# 7_SENSORS.net
KiCad netlist of a schematic drawn in Altium Designer
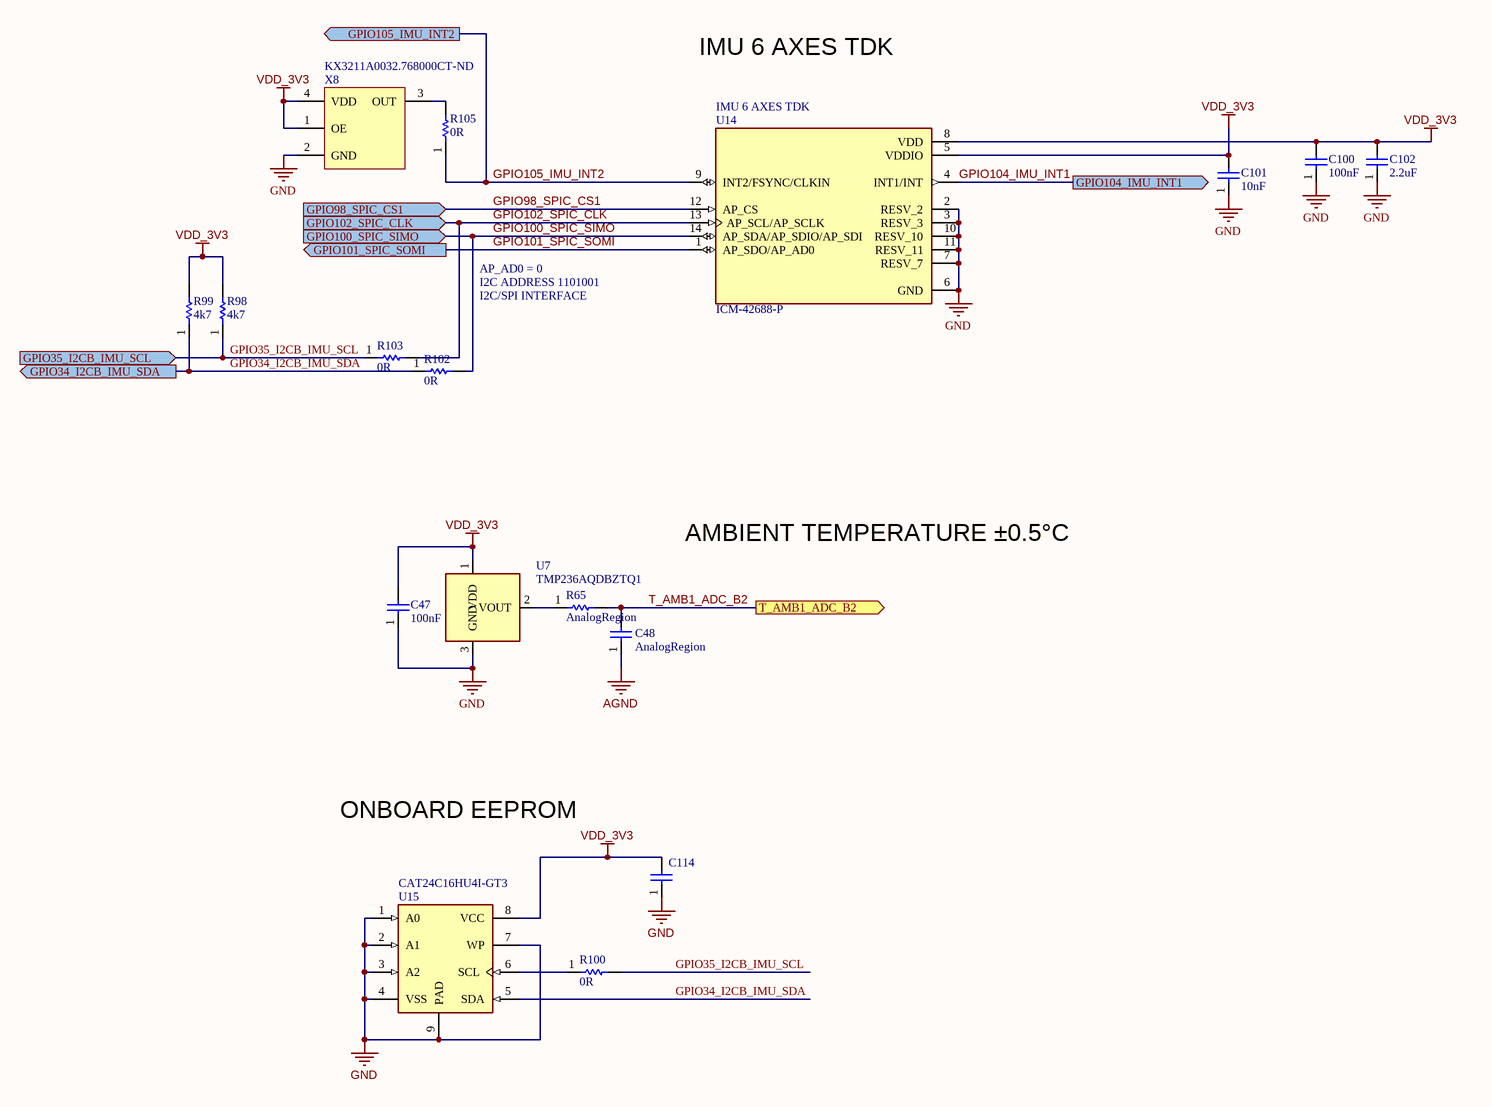
[diagram p0: [7] SENSORS.SchDoc]

(export (version "E")
  (design (tool "Eeschema 10.0.6"))
  (components
    (comp (ref "C47")
      (value "100nF")
      (footprint "CAPC1005X03N(0402)")
      (description "CAP CER 0.1UF 16V X7R 0402")
      (fields (field (name "MPN") "GRM155R71C104JA88D") (field (name "TOLERANCE") "5%"))
      (libsource (lib "IHMC_Altium_Lib") (part "100nF_16V_0402_CAP"))
    )
    (comp (ref "C48")
      (value "GCM1555C1H471JA16D")
      (footprint "CAPC1005X03N(0402)")
      (description "CAP CER 470PF 50V C0G/NP0 0402")
      (fields
        (field (name "TOLERANCE") "5%")
        (field (name "VOLTAGE") "50V")
        (field (name "CLASSNAME") "AnalogRegion")
      )
      (libsource (lib "IHMC_Altium_Lib") (part "470pF_50V_0402_CAP"))
    )
    (comp (ref "C100")
      (value "100nF")
      (footprint "CAPC1005X03N(0402)")
      (description "CAP CER 0.1UF 16V X7R 0402")
      (fields (field (name "MPN") "GRM155R71C104JA88D") (field (name "TOLERANCE") "5%"))
      (libsource (lib "IHMC_Altium_Lib") (part "100nF_16V_0402_CAP"))
    )
    (comp (ref "C101")
      (value "10nF")
      (footprint "CAPC1005X03N(0402)")
      (description "CAP CER 10000PF 50V X7R 0402")
      (fields (field (name "MPN") "CC0402KRX7R9BB103") (field (name "VOLTAGE") "50V"))
      (libsource (lib "IHMC_Altium_Lib") (part "10nF_50V_0402_CAP"))
    )
    (comp (ref "C102")
      (value "2.2uF")
      (footprint "CAPC1608X09N(0603)")
      (description "CAP CER 2.2UF 10V X5R 0603")
      (fields (field (name "MPN") "GRM188R61A225KE34D") (field (name "TOLERANCE") "10%"))
      (libsource (lib "IHMC_Altium_Lib") (part "2.2uF_10V_0603_CAP"))
    )
    (comp (ref "C114")
      (value "GRM155R71C104JA88D")
      (footprint "CAPC1005X03N(0402)")
      (description "CAP CER 0.1UF 16V X7R 0402")
      (fields (field (name "TOLERANCE") "5%"))
      (libsource (lib "IHMC_Altium_Lib") (part "100nF_16V_0402_CAP"))
    )
    (comp (ref "R65")
      (value "CRCW0402220RFKED")
      (footprint "RESC1005X06N(0402)")
      (description "RES SMD 220 OHM 1% 1/16W 0402")
      (fields (field (name "TOLERANCE") "1%.") (field (name "CLASSNAME") "AnalogRegion"))
      (libsource (lib "IHMC_Altium_Lib") (part "220_1/16W_0402_RES"))
    )
    (comp (ref "R98")
      (value "4k7")
      (footprint "RESC1608X09N(0603)")
      (description "RES SMD 4.7K OHM 1% 1/10W 0603")
      (fields (field (name "MPN") "CRCW06034K70FKEA") (field (name "DRAWN BY") "TC"))
      (libsource (lib "IHMC_Altium_Lib") (part "4k7_1/10W_0603_RES"))
    )
    (comp (ref "R99")
      (value "4k7")
      (footprint "RESC1608X09N(0603)")
      (description "RES SMD 4.7K OHM 1% 1/10W 0603")
      (fields (field (name "MPN") "CRCW06034K70FKEA") (field (name "DRAWN BY") "TC"))
      (libsource (lib "IHMC_Altium_Lib") (part "4k7_1/10W_0603_RES"))
    )
    (comp (ref "R100")
      (value "0R")
      (footprint "RESC1608X09N(0603)")
      (description "RES SMD 0 OHM JUMPER 1/10W 0603")
      (fields (field (name "MPN") "RC0603JR-070RL") (field (name "TOLERANCE") "Jumper"))
      (libsource (lib "IHMC_Altium_Lib") (part "0R_1/10W_0603_RES"))
    )
    (comp (ref "R102")
      (value "0R")
      (footprint "0402")
      (fields
        (field (name "MANUFACTURER") "Vishay Dale")
        (field (name "MANUFACTURER PART NUMBER") "RCS04020000Z0ED")
      )
      (libsource (lib "IHMC_Altium_Lib") (part "0R_1/5W_0402_RCS04020000Z0ED_RES"))
    )
    (comp (ref "R103")
      (value "0R")
      (footprint "0402")
      (fields
        (field (name "MANUFACTURER") "Vishay Dale")
        (field (name "MANUFACTURER PART NUMBER") "RCS04020000Z0ED")
      )
      (libsource (lib "IHMC_Altium_Lib") (part "0R_1/5W_0402_RCS04020000Z0ED_RES"))
    )
    (comp (ref "R105")
      (value "0R")
      (footprint "0402")
      (fields
        (field (name "MANUFACTURER") "Vishay Dale")
        (field (name "MANUFACTURER PART NUMBER") "RCS04020000Z0ED")
      )
      (libsource (lib "IHMC_Altium_Lib") (part "0R_1/5W_0402_RCS04020000Z0ED_RES"))
    )
    (comp (ref "U7")
      (value "TMP236AQDBZTQ1")
      (footprint "SOT23")
      (description "TMP23x-Q1 Automotive Grade, High-Accuracy Analog Output Temperature Sensors")
      (fields (field (name "MANUFACTURER") "Texas Instruments"))
      (libsource (lib "IHMC_Altium_Lib") (part "TMP236AQDBZTQ1_TEMP_SENSOR"))
    )
    (comp (ref "U14")
      (value "ICM-42688-P")
      (footprint "PQFN50P300X250X97-14N")
      (description "Accelerometer and Gyroscope 6-Axis MEMS Motion Tracking Device Digital-OUT 14-Pin LGA T/R")
      (fields (field (name "MANUFACTURER") "TDK InvenSense"))
      (libsource (lib "IHMC_Altium_Lib") (part "ICM-42688-P_IMU_6-axes"))
    )
    (comp (ref "U15")
      (value "CAT24C16HU4I-GT3")
      (footprint "UDFN8-EP")
      (description "EEPROM Serial-2Wire 16K-bit 2K x 8 1.8V/2.5V/3.3V/5V Automotive 8-Pin UDFN EP T/R")
      (fields (field (name "MANUFACTURER") "ON Semiconductor"))
      (libsource (lib "IHMC_Altium_Lib") (part "CAT24C16HU4I-GT3_EEPROM_16Kb"))
    )
    (comp (ref "X8")
      (value "32.768Khz_OSC_KX3211A0032.768000")
      (footprint "KX3211A0032.768000")
      (description "SMD Crystal Oscillator 0.032768MHz 3.3V 15pF 4-Pin CSMD")
      (fields
        (field (name "MANUFACTURER") "Diodes")
        (field (name "MANUFACTURER PART NUMBER") "KX3211A0032.768000")
        (field (name "SUPPLIER PART NUMBER 1") "KX3211A0032.768000CT-ND")
      )
      (libsource (lib "IHMC_Altium_Lib") (part "32.768Khz_OSC_KX3211A0032.768000"))
    )
  )
  (nets
    (net (code "1") (name "/GPIO34_I2CB_IMU_SDA") (class "Default")
      (node (ref "R102") (pin "1") (pinfunction "1_1") (pintype "passive"))
      (node (ref "R99") (pin "1") (pinfunction "1_1") (pintype "passive"))
      (node (ref "U15") (pin "5") (pinfunction "SDA_5") (pintype "input"))
    )
    (net (code "2") (name "/GPIO35_I2CB_IMU_SCL") (class "Default")
      (node (ref "R100") (pin "2") (pinfunction "2_2") (pintype "passive"))
      (node (ref "R103") (pin "1") (pinfunction "1_1") (pintype "passive"))
      (node (ref "R98") (pin "1") (pinfunction "1_1") (pintype "passive"))
    )
    (net (code "3") (name "/GPIO98_SPIC_CS1") (class "Default")
      (node (ref "U14") (pin "12") (pinfunction "AP_CS_12") (pintype "input"))
    )
    (net (code "4") (name "/GPIO100_SPIC_SIMO") (class "Default")
      (node (ref "R102") (pin "2") (pinfunction "2_2") (pintype "passive"))
      (node (ref "U14") (pin "14") (pinfunction "AP_SDA/AP_SDIO/AP_SDI_14") (pintype "bidirectional"))
    )
    (net (code "5") (name "/GPIO101_SPIC_SOMI") (class "Default")
      (node (ref "U14") (pin "1") (pinfunction "AP_SDO/AP_AD0_1") (pintype "bidirectional"))
    )
    (net (code "6") (name "/GPIO102_SPIC_CLK") (class "Default")
      (node (ref "R103") (pin "2") (pinfunction "2_2") (pintype "passive"))
      (node (ref "U14") (pin "13") (pinfunction "AP_SCL/AP_SCLK_13") (pintype "input"))
    )
    (net (code "7") (name "/GPIO104_IMU_INT1") (class "Default")
      (node (ref "U14") (pin "4") (pinfunction "INT1/INT_4") (pintype "output"))
    )
    (net (code "8") (name "/GPIO105_IMU_INT2") (class "Default")
      (node (ref "R105") (pin "1") (pinfunction "1_1") (pintype "passive"))
      (node (ref "U14") (pin "9") (pinfunction "INT2/FSYNC/CLKIN_9") (pintype "bidirectional"))
    )
    (net (code "9") (name "/T_AMB1_ADC_B2") (class "Default")
      (node (ref "C48") (pin "2") (pinfunction "2_2") (pintype "passive"))
      (node (ref "R65") (pin "2") (pinfunction "2_2") (pintype "passive"))
    )
    (net (code "10") (name "AGND") (class "Default")
      (node (ref "C48") (pin "1") (pinfunction "1_1") (pintype "passive"))
    )
    (net (code "11") (name "GND") (class "Default")
      (node (ref "C100") (pin "1") (pinfunction "1_1") (pintype "passive"))
      (node (ref "C101") (pin "1") (pinfunction "1_1") (pintype "passive"))
      (node (ref "C102") (pin "1") (pinfunction "1_1") (pintype "passive"))
      (node (ref "C114") (pin "1") (pinfunction "1_1") (pintype "passive"))
      (node (ref "C47") (pin "1") (pinfunction "1_1") (pintype "passive"))
      (node (ref "U14") (pin "10") (pinfunction "RESV_10_10") (pintype "passive"))
      (node (ref "U14") (pin "11") (pinfunction "RESV_11_11") (pintype "passive"))
      (node (ref "U14") (pin "2") (pinfunction "RESV_2_2") (pintype "passive"))
      (node (ref "U14") (pin "3") (pinfunction "RESV_3_3") (pintype "passive"))
      (node (ref "U14") (pin "6") (pinfunction "GND_6") (pintype "power_in"))
      (node (ref "U14") (pin "7") (pinfunction "RESV_7_7") (pintype "passive"))
      (node (ref "U15") (pin "1") (pinfunction "A0_1") (pintype "input"))
      (node (ref "U15") (pin "2") (pinfunction "A1_2") (pintype "input"))
      (node (ref "U15") (pin "3") (pinfunction "A2_3") (pintype "input"))
      (node (ref "U15") (pin "4") (pinfunction "VSS_4") (pintype "power_in"))
      (node (ref "U15") (pin "7") (pinfunction "WP_7") (pintype "passive"))
      (node (ref "U15") (pin "9") (pinfunction "PAD_9") (pintype "power_in"))
      (node (ref "U7") (pin "3") (pinfunction "GND_3") (pintype "passive"))
      (node (ref "X8") (pin "2") (pinfunction "GND_2") (pintype "passive"))
    )
    (net (code "12") (name "Net-(U7-VOUT)") (class "Default")
      (node (ref "R65") (pin "1") (pinfunction "1_1") (pintype "passive"))
      (node (ref "U7") (pin "2") (pinfunction "VOUT_2") (pintype "passive"))
    )
    (net (code "13") (name "Net-(U15-SCL)") (class "Default")
      (node (ref "R100") (pin "1") (pinfunction "1_1") (pintype "passive"))
      (node (ref "U15") (pin "6") (pinfunction "SCL_6") (pintype "input"))
    )
    (net (code "14") (name "Net-(X8-OUT)") (class "Default")
      (node (ref "R105") (pin "2") (pinfunction "2_2") (pintype "passive"))
      (node (ref "X8") (pin "3") (pinfunction "OUT_3") (pintype "passive"))
    )
    (net (code "15") (name "VDD_3V3") (class "Default")
      (node (ref "C100") (pin "2") (pinfunction "2_2") (pintype "passive"))
      (node (ref "C101") (pin "2") (pinfunction "2_2") (pintype "passive"))
      (node (ref "C102") (pin "2") (pinfunction "2_2") (pintype "passive"))
      (node (ref "C114") (pin "2") (pinfunction "2_2") (pintype "passive"))
      (node (ref "C47") (pin "2") (pinfunction "2_2") (pintype "passive"))
      (node (ref "R98") (pin "2") (pinfunction "2_2") (pintype "passive"))
      (node (ref "R99") (pin "2") (pinfunction "2_2") (pintype "passive"))
      (node (ref "U14") (pin "5") (pinfunction "VDDIO_5") (pintype "power_in"))
      (node (ref "U14") (pin "8") (pinfunction "VDD_8") (pintype "power_in"))
      (node (ref "U15") (pin "8") (pinfunction "VCC_8") (pintype "power_in"))
      (node (ref "U7") (pin "1") (pinfunction "VDD_1") (pintype "passive"))
      (node (ref "X8") (pin "1") (pinfunction "OE_1") (pintype "passive"))
      (node (ref "X8") (pin "4") (pinfunction "VDD_4") (pintype "passive"))
    )
  )
)
